# eth.net
KiCad netlist of a schematic drawn in Altium Designer
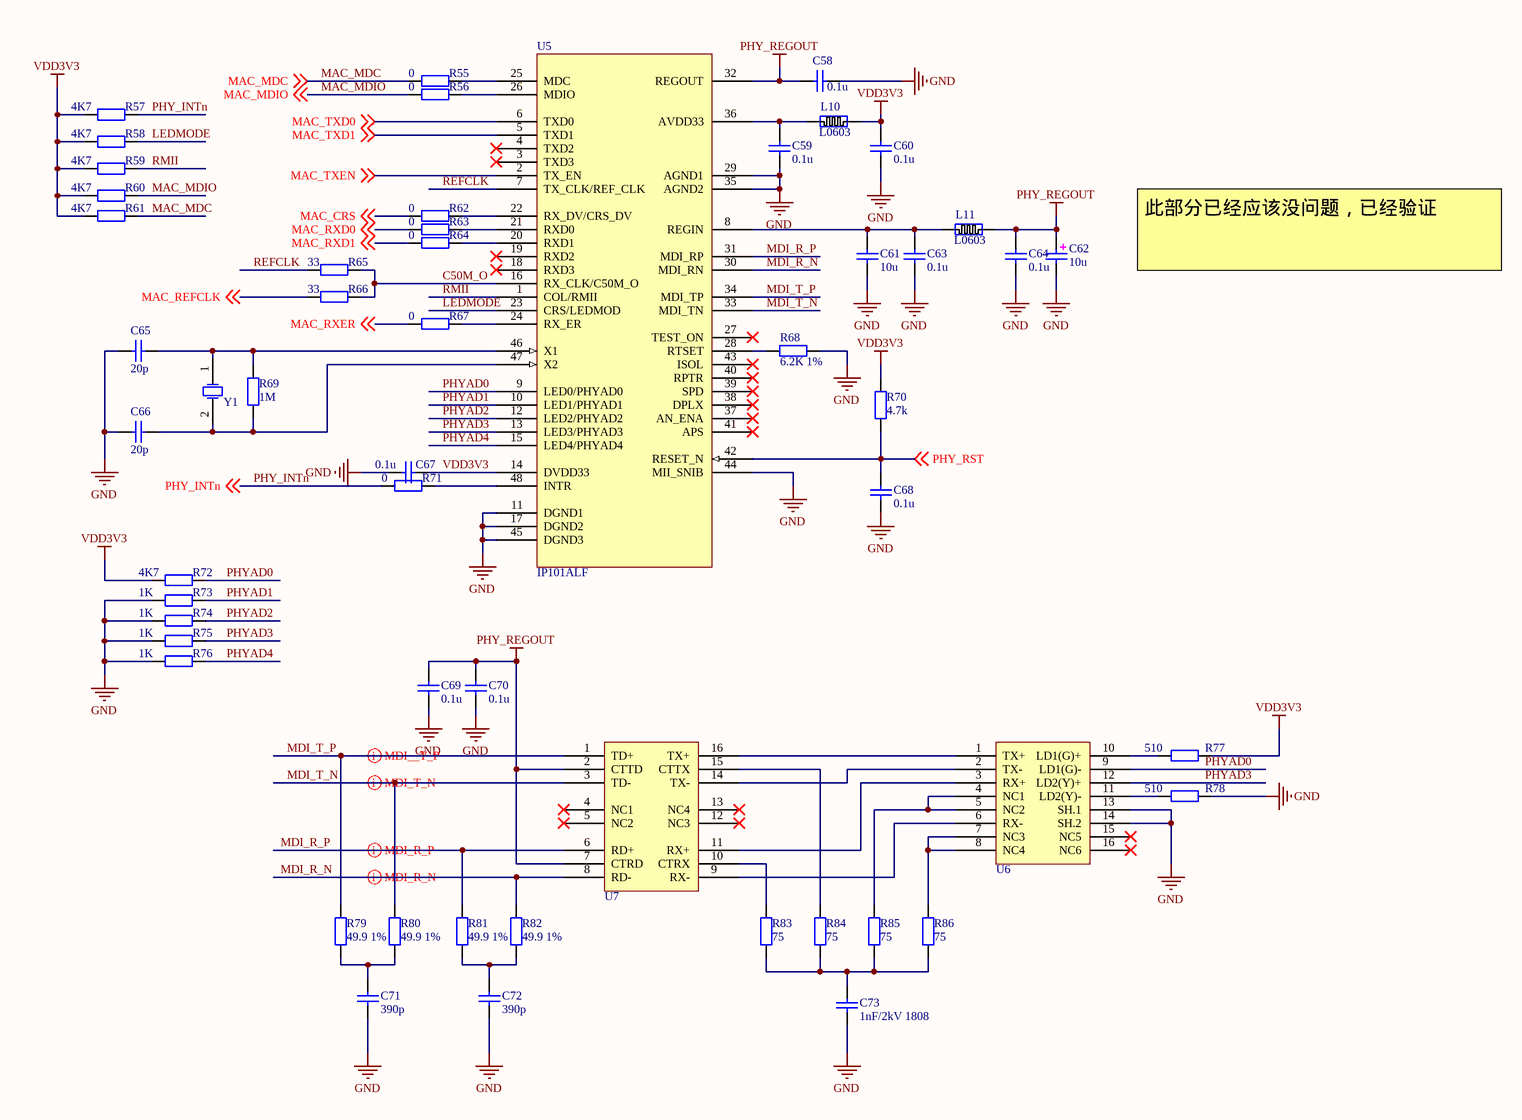
[diagram p0: eth.SchDoc]

(export (version "E")
  (design (tool "Eeschema 10.0.6"))
  (components
    (comp (ref "C58")
      (value "0.1u")
      (footprint "C0603")
      (description "0603 Capacitor without Polarity")
      (libsource (lib "lpc2368") (part "CAP0603"))
    )
    (comp (ref "C59")
      (value "0.1u")
      (footprint "C0603")
      (description "0603 Capacitor without Polarity")
      (libsource (lib "lpc2368") (part "CAP0603"))
    )
    (comp (ref "C60")
      (value "0.1u")
      (footprint "C0603")
      (description "0603 Capacitor without Polarity")
      (libsource (lib "lpc2368") (part "CAP0603"))
    )
    (comp (ref "C61")
      (value "10u")
      (footprint "C0603")
      (description "0603 Capacitor without Polarity")
      (libsource (lib "lpc2368") (part "CAP0603"))
    )
    (comp (ref "C62")
      (value "10u")
      (footprint "C1210")
      (description "钽电容1210封装")
      (libsource (lib "lpc2368") (part "DCAP"))
    )
    (comp (ref "C63")
      (value "0.1u")
      (footprint "C0603")
      (description "0603 Capacitor without Polarity")
      (libsource (lib "lpc2368") (part "CAP0603"))
    )
    (comp (ref "C64")
      (value "0.1u")
      (footprint "C0603")
      (description "0603 Capacitor without Polarity")
      (libsource (lib "lpc2368") (part "CAP0603"))
    )
    (comp (ref "C65")
      (value "20p")
      (footprint "C0603")
      (description "0603 Capacitor without Polarity")
      (libsource (lib "lpc2368") (part "CAP0603"))
    )
    (comp (ref "C66")
      (value "20p")
      (footprint "C0603")
      (description "0603 Capacitor without Polarity")
      (libsource (lib "lpc2368") (part "CAP0603"))
    )
    (comp (ref "C67")
      (value "0.1u")
      (footprint "C0603")
      (description "0603 Capacitor without Polarity")
      (libsource (lib "lpc2368") (part "CAP0603"))
    )
    (comp (ref "C68")
      (value "0.1u")
      (footprint "C0603")
      (description "0603 Capacitor without Polarity")
      (libsource (lib "lpc2368") (part "CAP0603"))
    )
    (comp (ref "C69")
      (value "0.1u")
      (footprint "C0603")
      (description "0603 Capacitor without Polarity")
      (libsource (lib "lpc2368") (part "CAP0603"))
    )
    (comp (ref "C70")
      (value "0.1u")
      (footprint "C0603")
      (description "0603 Capacitor without Polarity")
      (libsource (lib "lpc2368") (part "CAP0603"))
    )
    (comp (ref "C71")
      (value "390p")
      (footprint "C0603")
      (description "0603 Capacitor without Polarity")
      (libsource (lib "lpc2368") (part "CAP0603"))
    )
    (comp (ref "C72")
      (value "390p")
      (footprint "C0603")
      (description "0603 Capacitor without Polarity")
      (libsource (lib "lpc2368") (part "CAP0603"))
    )
    (comp (ref "C73")
      (value "1nF/2kV 1808")
      (footprint "C1808")
      (description "0603 Capacitor without Polarity")
      (libsource (lib "lpc2368") (part "CAP0603"))
    )
    (comp (ref "L10")
      (value "L0603")
      (footprint "L0603")
      (description "0603 Inductor")
      (libsource (lib "lpc2368") (part "L0603"))
    )
    (comp (ref "L11")
      (value "L0603")
      (footprint "L0603")
      (description "0603 Inductor")
      (libsource (lib "lpc2368") (part "L0603"))
    )
    (comp (ref "R55")
      (value "0")
      (footprint "R0603")
      (description "0603 Resistor")
      (libsource (lib "") (part "RES0603_1"))
    )
    (comp (ref "R56")
      (value "0")
      (footprint "R0603")
      (description "0603 Resistor")
      (libsource (lib "") (part "RES0603_1"))
    )
    (comp (ref "R57")
      (value "4K7")
      (footprint "R0603")
      (description "0603 Resistor")
      (libsource (lib "") (part "RES0603_1"))
    )
    (comp (ref "R58")
      (value "4K7")
      (footprint "R0603")
      (description "0603 Resistor")
      (libsource (lib "") (part "RES0603_1"))
    )
    (comp (ref "R59")
      (value "4K7")
      (footprint "R0603")
      (description "0603 Resistor")
      (libsource (lib "") (part "RES0603_1"))
    )
    (comp (ref "R60")
      (value "4K7")
      (footprint "R0603")
      (description "0603 Resistor")
      (libsource (lib "") (part "RES0603_1"))
    )
    (comp (ref "R61")
      (value "4K7")
      (footprint "R0603")
      (description "0603 Resistor")
      (libsource (lib "") (part "RES0603_1"))
    )
    (comp (ref "R62")
      (value "0")
      (footprint "R0603")
      (description "0603 Resistor")
      (libsource (lib "") (part "RES0603_1"))
    )
    (comp (ref "R63")
      (value "0")
      (footprint "R0603")
      (description "0603 Resistor")
      (libsource (lib "") (part "RES0603_1"))
    )
    (comp (ref "R64")
      (value "0")
      (footprint "R0603")
      (description "0603 Resistor")
      (libsource (lib "") (part "RES0603_1"))
    )
    (comp (ref "R65")
      (value "33")
      (footprint "R0603")
      (description "0603 Resistor")
      (libsource (lib "") (part "RES0603_1"))
    )
    (comp (ref "R66")
      (value "33")
      (footprint "R0603")
      (description "0603 Resistor")
      (libsource (lib "") (part "RES0603_1"))
    )
    (comp (ref "R67")
      (value "0")
      (footprint "R0603")
      (description "0603 Resistor")
      (libsource (lib "") (part "RES0603_1"))
    )
    (comp (ref "R68")
      (value "6.2K 1%")
      (footprint "R0603")
      (description "0603 Resistor")
      (libsource (lib "") (part "RES0603_1"))
    )
    (comp (ref "R69")
      (value "1M")
      (footprint "R0603")
      (description "0603 Resistor")
      (libsource (lib "lpc2368") (part "RES0603"))
    )
    (comp (ref "R70")
      (value "4.7k")
      (footprint "R0603")
      (description "0603 Resistor")
      (libsource (lib "lpc2368") (part "RES0603"))
    )
    (comp (ref "R71")
      (value "0")
      (footprint "R0603")
      (description "0603 Resistor")
      (libsource (lib "") (part "RES0603_1"))
    )
    (comp (ref "R72")
      (value "4K7")
      (footprint "R0603")
      (description "0603 Resistor")
      (libsource (lib "") (part "RES0603_1"))
    )
    (comp (ref "R73")
      (value "1K")
      (footprint "R0603")
      (description "0603 Resistor")
      (libsource (lib "") (part "RES0603_1"))
    )
    (comp (ref "R74")
      (value "1K")
      (footprint "R0603")
      (description "0603 Resistor")
      (libsource (lib "") (part "RES0603_1"))
    )
    (comp (ref "R75")
      (value "1K")
      (footprint "R0603")
      (description "0603 Resistor")
      (libsource (lib "") (part "RES0603_1"))
    )
    (comp (ref "R76")
      (value "1K")
      (footprint "R0603")
      (description "0603 Resistor")
      (libsource (lib "") (part "RES0603_1"))
    )
    (comp (ref "R77")
      (value "510")
      (footprint "R0603")
      (description "0603 Resistor")
      (libsource (lib "") (part "RES0603_2"))
    )
    (comp (ref "R78")
      (value "510")
      (footprint "R0603")
      (description "0603 Resistor")
      (libsource (lib "") (part "RES0603_2"))
    )
    (comp (ref "R79")
      (value "49.9 1%")
      (footprint "R0603")
      (description "0603 Resistor")
      (libsource (lib "lpc2368") (part "RES0603"))
    )
    (comp (ref "R80")
      (value "49.9 1%")
      (footprint "R0603")
      (description "0603 Resistor")
      (libsource (lib "lpc2368") (part "RES0603"))
    )
    (comp (ref "R81")
      (value "49.9 1%")
      (footprint "R0603")
      (description "0603 Resistor")
      (libsource (lib "lpc2368") (part "RES0603"))
    )
    (comp (ref "R82")
      (value "49.9 1%")
      (footprint "R0603")
      (description "0603 Resistor")
      (libsource (lib "lpc2368") (part "RES0603"))
    )
    (comp (ref "R83")
      (value "75")
      (footprint "R0603")
      (description "0603 Resistor")
      (libsource (lib "lpc2368") (part "RES0603"))
    )
    (comp (ref "R84")
      (value "75")
      (footprint "R0603")
      (description "0603 Resistor")
      (libsource (lib "lpc2368") (part "RES0603"))
    )
    (comp (ref "R85")
      (value "75")
      (footprint "R0603")
      (description "0603 Resistor")
      (libsource (lib "lpc2368") (part "RES0603"))
    )
    (comp (ref "R86")
      (value "75")
      (footprint "R0603")
      (description "0603 Resistor")
      (libsource (lib "lpc2368") (part "RES0603"))
    )
    (comp (ref "U5") (value "IP101ALF") (footprint "P48LQFP") (libsource (lib "lpc2368") (part "IP101ALF")))
    (comp (ref "U6")
      (value "48146-0010")
      (footprint "RJ45_1X1L_20U")
      (description "10/100Mbps ethernet RJ45 with LEDs")
      (libsource (lib "lpc2368") (part "48146-0010"))
    )
    (comp (ref "U7")
      (value "TS6121C")
      (footprint "TS6121C")
      (description "10/100Mbps Transformer")
      (libsource (lib "lpc2368") (part "TS6121C"))
    )
    (comp (ref "Y1")
      (value "XTAL")
      (footprint "XTAL-SMD-LP")
      (description "2Pin晶振")
      (libsource (lib "lpc2368") (part "XTAL"))
    )
  )
  (nets
    (net (code "1") (name "/C50M_O") (class "Default")
      (node (ref "R65") (pin "2") (pinfunction "2_2") (pintype "passive"))
      (node (ref "R66") (pin "2") (pinfunction "2_2") (pintype "passive"))
      (node (ref "U5") (pin "16") (pinfunction "RX_CLK/C50M_O_16") (pintype "passive"))
    )
    (net (code "2") (name "/LEDMODE") (class "Default")
      (node (ref "R58") (pin "2") (pinfunction "2_2") (pintype "passive"))
      (node (ref "U5") (pin "23") (pinfunction "CRS/LEDMOD_23") (pintype "passive"))
    )
    (net (code "3") (name "/MDI_R_N") (class "Default")
      (node (ref "R82") (pin "2") (pinfunction "2_2") (pintype "passive"))
      (node (ref "U5") (pin "30") (pinfunction "MDI_RN_30") (pintype "passive"))
      (node (ref "U7") (pin "8") (pinfunction "RD-_8") (pintype "passive"))
    )
    (net (code "4") (name "/MDI_R_P") (class "Default")
      (node (ref "R81") (pin "2") (pinfunction "2_2") (pintype "passive"))
      (node (ref "U5") (pin "31") (pinfunction "MDI_RP_31") (pintype "passive"))
      (node (ref "U7") (pin "6") (pinfunction "RD+_6") (pintype "passive"))
    )
    (net (code "5") (name "/MDI_T_N") (class "Default")
      (node (ref "R80") (pin "2") (pinfunction "2_2") (pintype "passive"))
      (node (ref "U5") (pin "33") (pinfunction "MDI_TN_33") (pintype "passive"))
      (node (ref "U7") (pin "3") (pinfunction "TD-_3") (pintype "passive"))
    )
    (net (code "6") (name "/MDI_T_P") (class "Default")
      (node (ref "R79") (pin "2") (pinfunction "2_2") (pintype "passive"))
      (node (ref "U5") (pin "34") (pinfunction "MDI_TP_34") (pintype "passive"))
      (node (ref "U7") (pin "1") (pinfunction "TD+_1") (pintype "passive"))
    )
    (net (code "7") (name "/PHYAD0") (class "Default")
      (node (ref "R72") (pin "2") (pinfunction "2_2") (pintype "passive"))
      (node (ref "U5") (pin "9") (pinfunction "LED0/PHYAD0_9") (pintype "passive"))
      (node (ref "U6") (pin "9") (pinfunction "LD1(G)-_9") (pintype "passive"))
    )
    (net (code "8") (name "/PHYAD1") (class "Default")
      (node (ref "R73") (pin "2") (pinfunction "2_2") (pintype "passive"))
      (node (ref "U5") (pin "10") (pinfunction "LED1/PHYAD1_10") (pintype "passive"))
    )
    (net (code "9") (name "/PHYAD2") (class "Default")
      (node (ref "R74") (pin "2") (pinfunction "2_2") (pintype "passive"))
      (node (ref "U5") (pin "12") (pinfunction "LED2/PHYAD2_12") (pintype "passive"))
    )
    (net (code "10") (name "/PHYAD3") (class "Default")
      (node (ref "R75") (pin "2") (pinfunction "2_2") (pintype "passive"))
      (node (ref "U5") (pin "13") (pinfunction "LED3/PHYAD3_13") (pintype "passive"))
      (node (ref "U6") (pin "12") (pinfunction "LD2(Y)+_12") (pintype "passive"))
    )
    (net (code "11") (name "/PHYAD4") (class "Default")
      (node (ref "R76") (pin "2") (pinfunction "2_2") (pintype "passive"))
      (node (ref "U5") (pin "15") (pinfunction "LED4/PHYAD4_15") (pintype "passive"))
    )
    (net (code "12") (name "/REFCLK") (class "Default")
      (node (ref "R65") (pin "1") (pinfunction "1_1") (pintype "passive"))
      (node (ref "U5") (pin "7") (pinfunction "TX_CLK/REF_CLK_7") (pintype "passive"))
    )
    (net (code "13") (name "/RMII") (class "Default")
      (node (ref "R59") (pin "2") (pinfunction "2_2") (pintype "passive"))
      (node (ref "U5") (pin "1") (pinfunction "COL/RMII_1") (pintype "passive"))
    )
    (net (code "14") (name "GND") (class "Default")
      (node (ref "C58") (pin "1") (pinfunction "1_1") (pintype "passive"))
      (node (ref "C59") (pin "1") (pinfunction "1_1") (pintype "passive"))
      (node (ref "C60") (pin "1") (pinfunction "1_1") (pintype "passive"))
      (node (ref "C61") (pin "1") (pinfunction "1_1") (pintype "passive"))
      (node (ref "C62") (pin "2") (pinfunction "2_2") (pintype "passive"))
      (node (ref "C63") (pin "1") (pinfunction "1_1") (pintype "passive"))
      (node (ref "C64") (pin "1") (pinfunction "1_1") (pintype "passive"))
      (node (ref "C65") (pin "1") (pinfunction "1_1") (pintype "passive"))
      (node (ref "C66") (pin "1") (pinfunction "1_1") (pintype "passive"))
      (node (ref "C67") (pin "1") (pinfunction "1_1") (pintype "passive"))
      (node (ref "C68") (pin "1") (pinfunction "1_1") (pintype "passive"))
      (node (ref "C69") (pin "1") (pinfunction "1_1") (pintype "passive"))
      (node (ref "C70") (pin "1") (pinfunction "1_1") (pintype "passive"))
      (node (ref "C71") (pin "1") (pinfunction "1_1") (pintype "passive"))
      (node (ref "C72") (pin "1") (pinfunction "1_1") (pintype "passive"))
      (node (ref "C73") (pin "1") (pinfunction "1_1") (pintype "passive"))
      (node (ref "R68") (pin "2") (pinfunction "2_2") (pintype "passive"))
      (node (ref "R73") (pin "1") (pinfunction "1_1") (pintype "passive"))
      (node (ref "R74") (pin "1") (pinfunction "1_1") (pintype "passive"))
      (node (ref "R75") (pin "1") (pinfunction "1_1") (pintype "passive"))
      (node (ref "R76") (pin "1") (pinfunction "1_1") (pintype "passive"))
      (node (ref "R78") (pin "1") (pinfunction "1_1") (pintype "passive"))
      (node (ref "U5") (pin "11") (pinfunction "DGND1_11") (pintype "passive"))
      (node (ref "U5") (pin "17") (pinfunction "DGND2_17") (pintype "passive"))
      (node (ref "U5") (pin "29") (pinfunction "AGND1_29") (pintype "passive"))
      (node (ref "U5") (pin "35") (pinfunction "AGND2_35") (pintype "passive"))
      (node (ref "U5") (pin "44") (pinfunction "MII_SNIB_44") (pintype "passive"))
      (node (ref "U5") (pin "45") (pinfunction "DGND3_45") (pintype "passive"))
      (node (ref "U6") (pin "13") (pinfunction "SH.1_13") (pintype "passive"))
      (node (ref "U6") (pin "14") (pinfunction "SH.2_14") (pintype "passive"))
    )
    (net (code "15") (name "MAC_CRS") (class "Default")
      (node (ref "R62") (pin "1") (pinfunction "1_1") (pintype "passive"))
    )
    (net (code "16") (name "MAC_MDC") (class "Default")
      (node (ref "R55") (pin "1") (pinfunction "1_1") (pintype "passive"))
      (node (ref "R61") (pin "2") (pinfunction "2_2") (pintype "passive"))
    )
    (net (code "17") (name "MAC_MDIO") (class "Default")
      (node (ref "R56") (pin "1") (pinfunction "1_1") (pintype "passive"))
      (node (ref "R60") (pin "2") (pinfunction "2_2") (pintype "passive"))
    )
    (net (code "18") (name "MAC_REFCLK") (class "Default")
      (node (ref "R66") (pin "1") (pinfunction "1_1") (pintype "passive"))
    )
    (net (code "19") (name "MAC_RXD0") (class "Default")
      (node (ref "R63") (pin "1") (pinfunction "1_1") (pintype "passive"))
    )
    (net (code "20") (name "MAC_RXD1") (class "Default")
      (node (ref "R64") (pin "1") (pinfunction "1_1") (pintype "passive"))
    )
    (net (code "21") (name "MAC_RXER") (class "Default")
      (node (ref "R67") (pin "1") (pinfunction "1_1") (pintype "passive"))
    )
    (net (code "22") (name "MAC_TXD0") (class "Default")
      (node (ref "U5") (pin "6") (pinfunction "TXD0_6") (pintype "passive"))
    )
    (net (code "23") (name "MAC_TXD1") (class "Default")
      (node (ref "U5") (pin "5") (pinfunction "TXD1_5") (pintype "passive"))
    )
    (net (code "24") (name "MAC_TXEN") (class "Default")
      (node (ref "U5") (pin "2") (pinfunction "TX_EN_2") (pintype "passive"))
    )
    (net (code "25") (name "Net-(C71-Pad2)") (class "Default")
      (node (ref "C71") (pin "2") (pinfunction "2_2") (pintype "passive"))
      (node (ref "R79") (pin "1") (pinfunction "1_1") (pintype "passive"))
      (node (ref "R80") (pin "1") (pinfunction "1_1") (pintype "passive"))
    )
    (net (code "26") (name "Net-(C72-Pad2)") (class "Default")
      (node (ref "C72") (pin "2") (pinfunction "2_2") (pintype "passive"))
      (node (ref "R81") (pin "1") (pinfunction "1_1") (pintype "passive"))
      (node (ref "R82") (pin "1") (pinfunction "1_1") (pintype "passive"))
    )
    (net (code "27") (name "Net-(C73-Pad2)") (class "Default")
      (node (ref "C73") (pin "2") (pinfunction "2_2") (pintype "passive"))
      (node (ref "R83") (pin "1") (pinfunction "1_1") (pintype "passive"))
      (node (ref "R84") (pin "1") (pinfunction "1_1") (pintype "passive"))
      (node (ref "R85") (pin "1") (pinfunction "1_1") (pintype "passive"))
      (node (ref "R86") (pin "1") (pinfunction "1_1") (pintype "passive"))
    )
    (net (code "28") (name "Net-(U5-AVDD33)") (class "Default")
      (node (ref "C59") (pin "2") (pinfunction "2_2") (pintype "passive"))
      (node (ref "L10") (pin "1") (pinfunction "1_1") (pintype "passive"))
      (node (ref "U5") (pin "36") (pinfunction "AVDD33_36") (pintype "passive"))
    )
    (net (code "29") (name "Net-(U5-INTR)") (class "Default")
      (node (ref "R71") (pin "2") (pinfunction "2_2") (pintype "passive"))
      (node (ref "U5") (pin "48") (pinfunction "INTR_48") (pintype "passive"))
    )
    (net (code "30") (name "Net-(U5-MDC)") (class "Default")
      (node (ref "R55") (pin "2") (pinfunction "2_2") (pintype "passive"))
      (node (ref "U5") (pin "25") (pinfunction "MDC_25") (pintype "passive"))
    )
    (net (code "31") (name "Net-(U5-MDIO)") (class "Default")
      (node (ref "R56") (pin "2") (pinfunction "2_2") (pintype "passive"))
      (node (ref "U5") (pin "26") (pinfunction "MDIO_26") (pintype "passive"))
    )
    (net (code "32") (name "Net-(U5-REGIN)") (class "Default")
      (node (ref "C61") (pin "2") (pinfunction "2_2") (pintype "passive"))
      (node (ref "C63") (pin "2") (pinfunction "2_2") (pintype "passive"))
      (node (ref "L11") (pin "1") (pinfunction "1_1") (pintype "passive"))
      (node (ref "U5") (pin "8") (pinfunction "REGIN_8") (pintype "passive"))
    )
    (net (code "33") (name "Net-(U5-RTSET)") (class "Default")
      (node (ref "R68") (pin "1") (pinfunction "1_1") (pintype "passive"))
      (node (ref "U5") (pin "28") (pinfunction "RTSET_28") (pintype "passive"))
    )
    (net (code "34") (name "Net-(U5-RXD0)") (class "Default")
      (node (ref "R63") (pin "2") (pinfunction "2_2") (pintype "passive"))
      (node (ref "U5") (pin "21") (pinfunction "RXD0_21") (pintype "passive"))
    )
    (net (code "35") (name "Net-(U5-RXD1)") (class "Default")
      (node (ref "R64") (pin "2") (pinfunction "2_2") (pintype "passive"))
      (node (ref "U5") (pin "20") (pinfunction "RXD1_20") (pintype "passive"))
    )
    (net (code "36") (name "Net-(U5-RX_DV{slash}CRS_DV)") (class "Default")
      (node (ref "R62") (pin "2") (pinfunction "2_2") (pintype "passive"))
      (node (ref "U5") (pin "22") (pinfunction "RX_DV/CRS_DV_22") (pintype "passive"))
    )
    (net (code "37") (name "Net-(U5-RX_ER)") (class "Default")
      (node (ref "R67") (pin "2") (pinfunction "2_2") (pintype "passive"))
      (node (ref "U5") (pin "24") (pinfunction "RX_ER_24") (pintype "passive"))
    )
    (net (code "38") (name "Net-(U5-X1)") (class "Default")
      (node (ref "C65") (pin "2") (pinfunction "2_2") (pintype "passive"))
      (node (ref "R69") (pin "2") (pinfunction "2_2") (pintype "passive"))
      (node (ref "U5") (pin "46") (pinfunction "X1_46") (pintype "input"))
      (node (ref "Y1") (pin "1") (pinfunction "OSC1_1") (pintype "passive"))
    )
    (net (code "39") (name "Net-(U5-X2)") (class "Default")
      (node (ref "C66") (pin "2") (pinfunction "2_2") (pintype "passive"))
      (node (ref "R69") (pin "1") (pinfunction "1_1") (pintype "passive"))
      (node (ref "U5") (pin "47") (pinfunction "X2_47") (pintype "input"))
      (node (ref "Y1") (pin "2") (pinfunction "OSC2_2") (pintype "passive"))
    )
    (net (code "40") (name "Net-(U6-LD1(G)+)") (class "Default")
      (node (ref "R77") (pin "2") (pinfunction "2_2") (pintype "passive"))
      (node (ref "U6") (pin "10") (pinfunction "LD1(G)+_10") (pintype "passive"))
    )
    (net (code "41") (name "Net-(U6-LD2(Y)-)") (class "Default")
      (node (ref "R78") (pin "2") (pinfunction "2_2") (pintype "passive"))
      (node (ref "U6") (pin "11") (pinfunction "LD2(Y)-_11") (pintype "passive"))
    )
    (net (code "42") (name "Net-(U6-NC1)") (class "Default")
      (node (ref "R85") (pin "2") (pinfunction "2_2") (pintype "passive"))
      (node (ref "U6") (pin "4") (pinfunction "NC1_4") (pintype "passive"))
      (node (ref "U6") (pin "5") (pinfunction "NC2_5") (pintype "passive"))
    )
    (net (code "43") (name "Net-(U6-NC3)") (class "Default")
      (node (ref "R86") (pin "2") (pinfunction "2_2") (pintype "passive"))
      (node (ref "U6") (pin "7") (pinfunction "NC3_7") (pintype "passive"))
      (node (ref "U6") (pin "8") (pinfunction "NC4_8") (pintype "passive"))
    )
    (net (code "44") (name "Net-(U6-RX+)") (class "Default")
      (node (ref "U6") (pin "3") (pinfunction "RX+_3") (pintype "passive"))
      (node (ref "U7") (pin "11") (pinfunction "RX+_11") (pintype "passive"))
    )
    (net (code "45") (name "Net-(U6-RX-)") (class "Default")
      (node (ref "U6") (pin "6") (pinfunction "RX-_6") (pintype "passive"))
      (node (ref "U7") (pin "9") (pinfunction "RX-_9") (pintype "passive"))
    )
    (net (code "46") (name "Net-(U6-TX+)") (class "Default")
      (node (ref "U6") (pin "1") (pinfunction "TX+_1") (pintype "passive"))
      (node (ref "U7") (pin "16") (pinfunction "TX+_16") (pintype "passive"))
    )
    (net (code "47") (name "Net-(U6-TX-)") (class "Default")
      (node (ref "U6") (pin "2") (pinfunction "TX-_2") (pintype "passive"))
      (node (ref "U7") (pin "14") (pinfunction "TX-_14") (pintype "passive"))
    )
    (net (code "48") (name "Net-(U7-CTRX)") (class "Default")
      (node (ref "R83") (pin "2") (pinfunction "2_2") (pintype "passive"))
      (node (ref "U7") (pin "10") (pinfunction "CTRX_10") (pintype "passive"))
    )
    (net (code "49") (name "Net-(U7-CTTX)") (class "Default")
      (node (ref "R84") (pin "2") (pinfunction "2_2") (pintype "passive"))
      (node (ref "U7") (pin "15") (pinfunction "CTTX_15") (pintype "passive"))
    )
    (net (code "50") (name "PHY_INTn") (class "Default")
      (node (ref "R57") (pin "2") (pinfunction "2_2") (pintype "passive"))
      (node (ref "R71") (pin "1") (pinfunction "1_1") (pintype "passive"))
    )
    (net (code "51") (name "PHY_REGOUT") (class "Default")
      (node (ref "C58") (pin "2") (pinfunction "2_2") (pintype "passive"))
      (node (ref "C62") (pin "1") (pinfunction "1_1") (pintype "passive"))
      (node (ref "C64") (pin "2") (pinfunction "2_2") (pintype "passive"))
      (node (ref "C69") (pin "2") (pinfunction "2_2") (pintype "passive"))
      (node (ref "C70") (pin "2") (pinfunction "2_2") (pintype "passive"))
      (node (ref "L11") (pin "2") (pinfunction "2_2") (pintype "passive"))
      (node (ref "U5") (pin "32") (pinfunction "REGOUT_32") (pintype "passive"))
      (node (ref "U7") (pin "2") (pinfunction "CTTD_2") (pintype "passive"))
      (node (ref "U7") (pin "7") (pinfunction "CTRD_7") (pintype "passive"))
    )
    (net (code "52") (name "PHY_RST") (class "Default")
      (node (ref "C68") (pin "2") (pinfunction "2_2") (pintype "passive"))
      (node (ref "R70") (pin "1") (pinfunction "1_1") (pintype "passive"))
      (node (ref "U5") (pin "42") (pinfunction "RESET_N_42") (pintype "input"))
    )
    (net (code "53") (name "VDD3V3") (class "Default")
      (node (ref "C60") (pin "2") (pinfunction "2_2") (pintype "passive"))
      (node (ref "C67") (pin "2") (pinfunction "2_2") (pintype "passive"))
      (node (ref "L10") (pin "2") (pinfunction "2_2") (pintype "passive"))
      (node (ref "R57") (pin "1") (pinfunction "1_1") (pintype "passive"))
      (node (ref "R58") (pin "1") (pinfunction "1_1") (pintype "passive"))
      (node (ref "R59") (pin "1") (pinfunction "1_1") (pintype "passive"))
      (node (ref "R60") (pin "1") (pinfunction "1_1") (pintype "passive"))
      (node (ref "R61") (pin "1") (pinfunction "1_1") (pintype "passive"))
      (node (ref "R70") (pin "2") (pinfunction "2_2") (pintype "passive"))
      (node (ref "R72") (pin "1") (pinfunction "1_1") (pintype "passive"))
      (node (ref "R77") (pin "1") (pinfunction "1_1") (pintype "passive"))
      (node (ref "U5") (pin "14") (pinfunction "DVDD33_14") (pintype "passive"))
    )
    (net (code "54") (name "unconnected-(U5-AN_ENA-Pad37)") (class "Default")
      (node (ref "U5") (pin "37") (pinfunction "AN_ENA_37") (pintype "passive+no_connect"))
    )
    (net (code "55") (name "unconnected-(U5-APS-Pad41)") (class "Default")
      (node (ref "U5") (pin "41") (pinfunction "APS_41") (pintype "passive+no_connect"))
    )
    (net (code "56") (name "unconnected-(U5-DPLX-Pad38)") (class "Default")
      (node (ref "U5") (pin "38") (pinfunction "DPLX_38") (pintype "passive+no_connect"))
    )
    (net (code "57") (name "unconnected-(U5-ISOL-Pad43)") (class "Default")
      (node (ref "U5") (pin "43") (pinfunction "ISOL_43") (pintype "passive+no_connect"))
    )
    (net (code "58") (name "unconnected-(U5-RPTR-Pad40)") (class "Default")
      (node (ref "U5") (pin "40") (pinfunction "RPTR_40") (pintype "passive+no_connect"))
    )
    (net (code "59") (name "unconnected-(U5-RXD2-Pad19)") (class "Default")
      (node (ref "U5") (pin "19") (pinfunction "RXD2_19") (pintype "passive+no_connect"))
    )
    (net (code "60") (name "unconnected-(U5-RXD3-Pad18)") (class "Default")
      (node (ref "U5") (pin "18") (pinfunction "RXD3_18") (pintype "passive+no_connect"))
    )
    (net (code "61") (name "unconnected-(U5-SPD-Pad39)") (class "Default")
      (node (ref "U5") (pin "39") (pinfunction "SPD_39") (pintype "passive+no_connect"))
    )
    (net (code "62") (name "unconnected-(U5-TEST_ON-Pad27)") (class "Default")
      (node (ref "U5") (pin "27") (pinfunction "TEST_ON_27") (pintype "passive+no_connect"))
    )
    (net (code "63") (name "unconnected-(U5-TXD2-Pad4)") (class "Default")
      (node (ref "U5") (pin "4") (pinfunction "TXD2_4") (pintype "passive+no_connect"))
    )
    (net (code "64") (name "unconnected-(U5-TXD3-Pad3)") (class "Default")
      (node (ref "U5") (pin "3") (pinfunction "TXD3_3") (pintype "passive+no_connect"))
    )
    (net (code "65") (name "unconnected-(U6-NC5-Pad15)") (class "Default")
      (node (ref "U6") (pin "15") (pinfunction "NC5_15") (pintype "passive+no_connect"))
    )
    (net (code "66") (name "unconnected-(U6-NC6-Pad16)") (class "Default")
      (node (ref "U6") (pin "16") (pinfunction "NC6_16") (pintype "passive+no_connect"))
    )
    (net (code "67") (name "unconnected-(U7-NC1-Pad4)") (class "Default")
      (node (ref "U7") (pin "4") (pinfunction "NC1_4") (pintype "passive+no_connect"))
    )
    (net (code "68") (name "unconnected-(U7-NC2-Pad5)") (class "Default")
      (node (ref "U7") (pin "5") (pinfunction "NC2_5") (pintype "passive+no_connect"))
    )
    (net (code "69") (name "unconnected-(U7-NC3-Pad12)") (class "Default")
      (node (ref "U7") (pin "12") (pinfunction "NC3_12") (pintype "passive+no_connect"))
    )
    (net (code "70") (name "unconnected-(U7-NC4-Pad13)") (class "Default")
      (node (ref "U7") (pin "13") (pinfunction "NC4_13") (pintype "passive+no_connect"))
    )
  )
)
